# blahblahVCA_MB.net
KiCad netlist of a schematic drawn in EAGLE
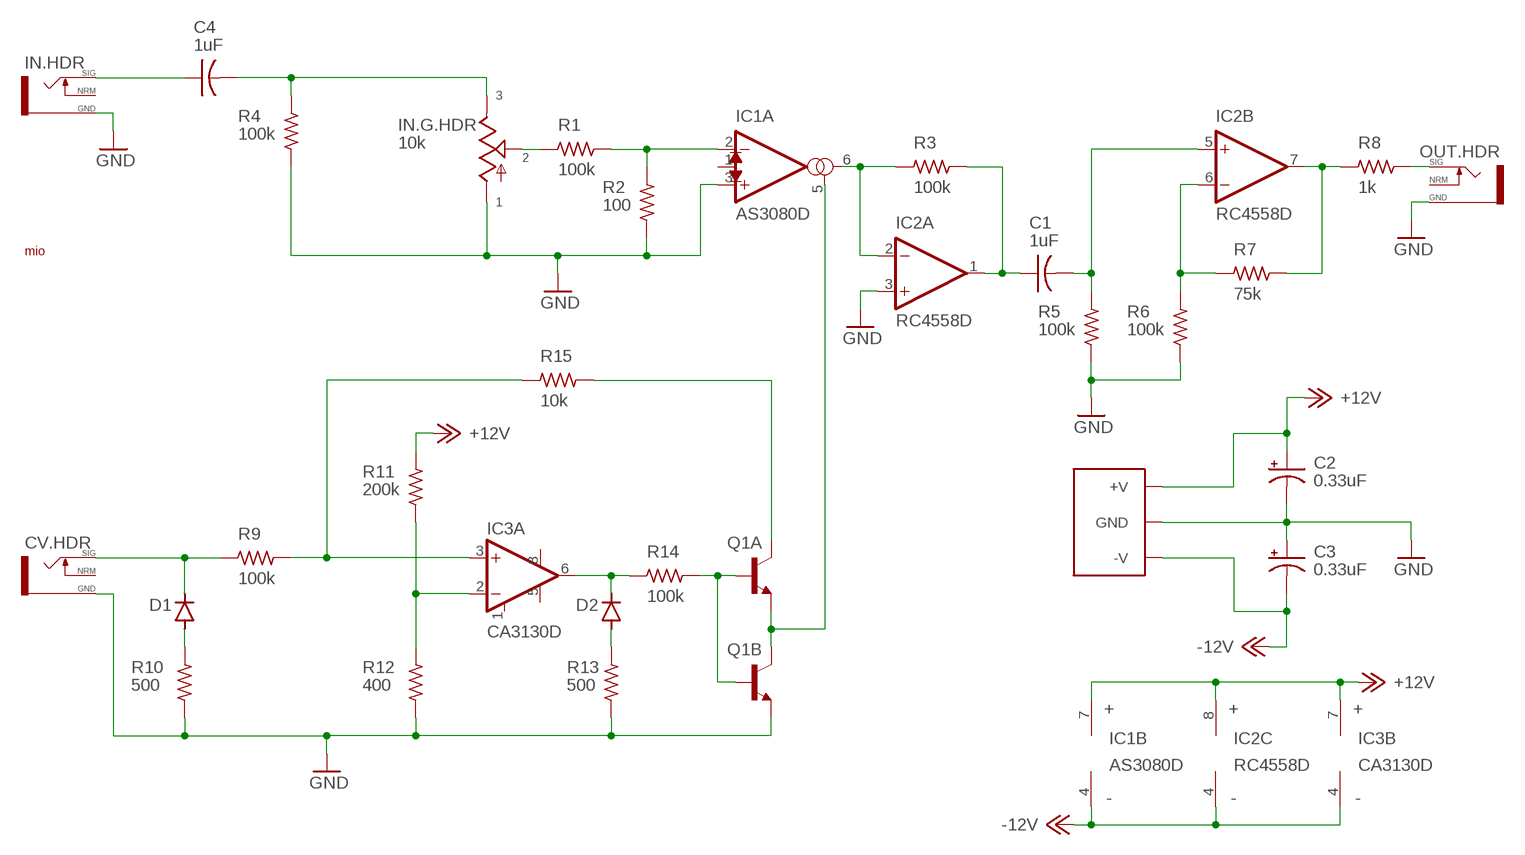
[diagram p0: schematic, sheet 1]

(export (version "E")
  (design (tool "Eeschema 10.0.6"))
  (components
    (comp (ref "C1")
      (value "1uF")
      (footprint "eagle-import:C05")
      (libsource (lib "eagle-import") (part "C-05"))
    )
    (comp (ref "C2")
      (value "0.33uF")
      (footprint "eagle-import:E025")
      (libsource (lib "eagle-import") (part "CPOL-E025"))
    )
    (comp (ref "C3")
      (value "0.33uF")
      (footprint "eagle-import:E025")
      (libsource (lib "eagle-import") (part "CPOL-E025"))
    )
    (comp (ref "C4")
      (value "1uF")
      (footprint "eagle-import:C05")
      (libsource (lib "eagle-import") (part "C-05"))
    )
    (comp (ref "CV.HDR")
      (value "MONOHDR")
      (footprint "eagle-import:HEADER")
      (libsource (lib "eagle-import") (part "MONOHDR"))
    )
    (comp (ref "D1")
      (value "D-123")
      (footprint "eagle-import:SOD-123")
      (libsource (lib "eagle-import") (part "D-123"))
    )
    (comp (ref "D2")
      (value "D-123")
      (footprint "eagle-import:SOD-123")
      (libsource (lib "eagle-import") (part "D-123"))
    )
    (comp (ref "IC1")
      (value "AS3080D")
      (footprint "eagle-import:DIL08")
      (libsource (lib "eagle-import") (part "AS3080D"))
    )
    (comp (ref "IC2")
      (value "RC4558D")
      (footprint "eagle-import:DIL08")
      (libsource (lib "eagle-import") (part "RC4558D"))
    )
    (comp (ref "IC3")
      (value "CA3130D")
      (footprint "eagle-import:DIL08")
      (libsource (lib "eagle-import") (part "CA3130D"))
    )
    (comp (ref "IN.G.HDR")
      (value "10k")
      (footprint "eagle-import:HEADER")
      (libsource (lib "eagle-import") (part "PHDR"))
    )
    (comp (ref "IN.HDR")
      (value "MONOHDR")
      (footprint "eagle-import:HEADER")
      (libsource (lib "eagle-import") (part "MONOHDR"))
    )
    (comp (ref "OUT.HDR")
      (value "MONOHDR")
      (footprint "eagle-import:HEADER")
      (libsource (lib "eagle-import") (part "MONOHDR"))
    )
    (comp (ref "Q1")
      (value "BCM847DS")
      (footprint "eagle-import:SOT-23-6")
      (libsource (lib "eagle-import") (part "BCM847DS"))
    )
    (comp (ref "R1")
      (value "100k")
      (footprint "eagle-import:R1206")
      (libsource (lib "eagle-import") (part "R-1206"))
    )
    (comp (ref "R2")
      (value "100")
      (footprint "eagle-import:R1206")
      (libsource (lib "eagle-import") (part "R-1206"))
    )
    (comp (ref "R3")
      (value "100k")
      (footprint "eagle-import:R1206")
      (libsource (lib "eagle-import") (part "R-1206"))
    )
    (comp (ref "R4")
      (value "100k")
      (footprint "eagle-import:R1206")
      (libsource (lib "eagle-import") (part "R-1206"))
    )
    (comp (ref "R5")
      (value "100k")
      (footprint "eagle-import:R1206")
      (libsource (lib "eagle-import") (part "R-1206"))
    )
    (comp (ref "R6")
      (value "100k")
      (footprint "eagle-import:R1206")
      (libsource (lib "eagle-import") (part "R-1206"))
    )
    (comp (ref "R7")
      (value "75k")
      (footprint "eagle-import:R1206")
      (libsource (lib "eagle-import") (part "R-1206"))
    )
    (comp (ref "R8")
      (value "1k")
      (footprint "eagle-import:R1206")
      (libsource (lib "eagle-import") (part "R-1206"))
    )
    (comp (ref "R9")
      (value "100k")
      (footprint "eagle-import:R1206")
      (libsource (lib "eagle-import") (part "R-1206"))
    )
    (comp (ref "R10")
      (value "500")
      (footprint "eagle-import:R1206")
      (libsource (lib "eagle-import") (part "R-1206"))
    )
    (comp (ref "R11")
      (value "200k")
      (footprint "eagle-import:R1206")
      (libsource (lib "eagle-import") (part "R-1206"))
    )
    (comp (ref "R12")
      (value "400")
      (footprint "eagle-import:R1206")
      (libsource (lib "eagle-import") (part "R-1206"))
    )
    (comp (ref "R13")
      (value "500")
      (footprint "eagle-import:R1206")
      (libsource (lib "eagle-import") (part "R-1206"))
    )
    (comp (ref "R14")
      (value "100k")
      (footprint "eagle-import:R1206")
      (libsource (lib "eagle-import") (part "R-1206"))
    )
    (comp (ref "R15")
      (value "10k")
      (footprint "eagle-import:R1206")
      (libsource (lib "eagle-import") (part "R-1206"))
    )
    (comp (ref "U$1")
      (value "10PIN-PWR")
      (footprint "eagle-import:10PIN-HEADER")
      (libsource (lib "eagle-import") (part "10PIN-PWR"))
    )
    (comp (ref "U$2")
      (value "MIO")
      (footprint "eagle-import:MIO")
      (libsource (lib "eagle-import") (part "MIO"))
    )
  )
  (nets
    (net (code "1") (name "+12V") (class "Default")
      (node (ref "C2") (pin "+") (pinfunction "+_+") (pintype "passive"))
      (node (ref "IC1") (pin "7") (pinfunction "V+_7") (pintype "power_in"))
      (node (ref "IC2") (pin "8") (pinfunction "V+_8") (pintype "power_in"))
      (node (ref "IC3") (pin "7") (pinfunction "V+_7") (pintype "power_in"))
      (node (ref "R11") (pin "2") (pinfunction "2_2") (pintype "passive"))
      (node (ref "U$1") (pin "10") (pinfunction "+V_10") (pintype "bidirectional"))
      (node (ref "U$1") (pin "9") (pinfunction "+V_9") (pintype "bidirectional"))
    )
    (net (code "2") (name "-12V") (class "Default")
      (node (ref "C3") (pin "-") (pinfunction "-_-") (pintype "passive"))
      (node (ref "IC1") (pin "4") (pinfunction "V-_4") (pintype "power_in"))
      (node (ref "IC2") (pin "4") (pinfunction "V-_4") (pintype "power_in"))
      (node (ref "IC3") (pin "4") (pinfunction "V-_4") (pintype "power_in"))
      (node (ref "U$1") (pin "1") (pinfunction "-V_1") (pintype "bidirectional"))
      (node (ref "U$1") (pin "2") (pinfunction "-V_2") (pintype "bidirectional"))
    )
    (net (code "3") (name "GND") (class "Default")
      (node (ref "C2") (pin "-") (pinfunction "-_-") (pintype "passive"))
      (node (ref "C3") (pin "+") (pinfunction "+_+") (pintype "passive"))
      (node (ref "CV.HDR") (pin "GND") (pinfunction "SLEEVE-GND_GND") (pintype "passive"))
      (node (ref "IC1") (pin "3") (pinfunction "NON-INVERTING(+)_3") (pintype "input"))
      (node (ref "IC2") (pin "3") (pinfunction "NON-INVERTING(+)_3") (pintype "input"))
      (node (ref "IN.G.HDR") (pin "1") (pinfunction "1_1") (pintype "passive"))
      (node (ref "IN.HDR") (pin "GND") (pinfunction "SLEEVE-GND_GND") (pintype "passive"))
      (node (ref "OUT.HDR") (pin "GND") (pinfunction "SLEEVE-GND_GND") (pintype "passive"))
      (node (ref "Q1") (pin "4") (pinfunction "E_4") (pintype "bidirectional"))
      (node (ref "R10") (pin "1") (pinfunction "1_1") (pintype "passive"))
      (node (ref "R12") (pin "1") (pinfunction "1_1") (pintype "passive"))
      (node (ref "R13") (pin "1") (pinfunction "1_1") (pintype "passive"))
      (node (ref "R2") (pin "1") (pinfunction "1_1") (pintype "passive"))
      (node (ref "R4") (pin "1") (pinfunction "1_1") (pintype "passive"))
      (node (ref "R5") (pin "1") (pinfunction "1_1") (pintype "passive"))
      (node (ref "R6") (pin "1") (pinfunction "1_1") (pintype "passive"))
      (node (ref "U$1") (pin "3") (pinfunction "GND_3") (pintype "bidirectional"))
      (node (ref "U$1") (pin "4") (pinfunction "GND_4") (pintype "bidirectional"))
      (node (ref "U$1") (pin "5") (pinfunction "GND_5") (pintype "bidirectional"))
      (node (ref "U$1") (pin "6") (pinfunction "GND_6") (pintype "bidirectional"))
      (node (ref "U$1") (pin "7") (pinfunction "GND_7") (pintype "bidirectional"))
      (node (ref "U$1") (pin "8") (pinfunction "GND_8") (pintype "bidirectional"))
    )
    (net (code "4") (name "Net-(C4-Pad1)") (class "Default")
      (node (ref "C4") (pin "1") (pinfunction "1_1") (pintype "passive"))
      (node (ref "IN.HDR") (pin "TIP-SIG") (pinfunction "TIP-SIG_TIP-SIG") (pintype "passive"))
    )
    (net (code "5") (name "Net-(C4-Pad2)") (class "Default")
      (node (ref "C4") (pin "2") (pinfunction "2_2") (pintype "passive"))
      (node (ref "IN.G.HDR") (pin "3") (pinfunction "3_3") (pintype "passive"))
      (node (ref "R4") (pin "2") (pinfunction "2_2") (pintype "passive"))
    )
    (net (code "6") (name "Net-(CV.HDR-PadTIP-SIG)") (class "Default")
      (node (ref "CV.HDR") (pin "TIP-SIG") (pinfunction "TIP-SIG_TIP-SIG") (pintype "passive"))
      (node (ref "D1") (pin "C") (pinfunction "C_C") (pintype "passive"))
      (node (ref "R9") (pin "1") (pinfunction "1_1") (pintype "passive"))
    )
    (net (code "7") (name "Net-(D1-PadA)") (class "Default")
      (node (ref "D1") (pin "A") (pinfunction "A_A") (pintype "passive"))
      (node (ref "R10") (pin "2") (pinfunction "2_2") (pintype "passive"))
    )
    (net (code "8") (name "Net-(D2-PadA)") (class "Default")
      (node (ref "D2") (pin "A") (pinfunction "A_A") (pintype "passive"))
      (node (ref "R13") (pin "2") (pinfunction "2_2") (pintype "passive"))
    )
    (net (code "9") (name "Net-(IC1A-I-BIAS)") (class "Default")
      (node (ref "IC1") (pin "5") (pinfunction "I-BIAS_5") (pintype "input"))
      (node (ref "Q1") (pin "1") (pinfunction "E_1") (pintype "bidirectional"))
      (node (ref "Q1") (pin "3") (pinfunction "C_3") (pintype "bidirectional"))
    )
    (net (code "10") (name "Net-(IC1A-INVERTING(-))") (class "Default")
      (node (ref "IC1") (pin "2") (pinfunction "INVERTING(-)_2") (pintype "input"))
      (node (ref "R1") (pin "2") (pinfunction "2_2") (pintype "passive"))
      (node (ref "R2") (pin "2") (pinfunction "2_2") (pintype "passive"))
    )
    (net (code "11") (name "Net-(IC1A-OUT)") (class "Default")
      (node (ref "IC1") (pin "6") (pinfunction "OUT_6") (pintype "output"))
      (node (ref "IC2") (pin "2") (pinfunction "INVERTING(-)_2") (pintype "input"))
      (node (ref "R3") (pin "1") (pinfunction "1_1") (pintype "passive"))
    )
    (net (code "12") (name "Net-(IC2A-OUT)") (class "Default")
      (node (ref "C1") (pin "1") (pinfunction "1_1") (pintype "passive"))
      (node (ref "IC2") (pin "1") (pinfunction "OUT_1") (pintype "output"))
      (node (ref "R3") (pin "2") (pinfunction "2_2") (pintype "passive"))
    )
    (net (code "13") (name "Net-(IC2B-INVERTING(-))") (class "Default")
      (node (ref "IC2") (pin "6") (pinfunction "INVERTING(-)_6") (pintype "input"))
      (node (ref "R6") (pin "2") (pinfunction "2_2") (pintype "passive"))
      (node (ref "R7") (pin "1") (pinfunction "1_1") (pintype "passive"))
    )
    (net (code "14") (name "Net-(IC2B-NON-INVERTING(+))") (class "Default")
      (node (ref "C1") (pin "2") (pinfunction "2_2") (pintype "passive"))
      (node (ref "IC2") (pin "5") (pinfunction "NON-INVERTING(+)_5") (pintype "input"))
      (node (ref "R5") (pin "2") (pinfunction "2_2") (pintype "passive"))
    )
    (net (code "15") (name "Net-(IC2B-OUT)") (class "Default")
      (node (ref "IC2") (pin "7") (pinfunction "OUT_7") (pintype "output"))
      (node (ref "R7") (pin "2") (pinfunction "2_2") (pintype "passive"))
      (node (ref "R8") (pin "1") (pinfunction "1_1") (pintype "passive"))
    )
    (net (code "16") (name "Net-(IC3A-INVERTINGA(-))") (class "Default")
      (node (ref "IC3") (pin "2") (pinfunction "INVERTINGA(-)_2") (pintype "input"))
      (node (ref "R11") (pin "1") (pinfunction "1_1") (pintype "passive"))
      (node (ref "R12") (pin "2") (pinfunction "2_2") (pintype "passive"))
    )
    (net (code "17") (name "Net-(IC3A-NON-INVERTING(+))") (class "Default")
      (node (ref "IC3") (pin "3") (pinfunction "NON-INVERTING(+)_3") (pintype "input"))
      (node (ref "R15") (pin "1") (pinfunction "1_1") (pintype "passive"))
      (node (ref "R9") (pin "2") (pinfunction "2_2") (pintype "passive"))
    )
    (net (code "18") (name "Net-(IC3A-OUT)") (class "Default")
      (node (ref "D2") (pin "C") (pinfunction "C_C") (pintype "passive"))
      (node (ref "IC3") (pin "6") (pinfunction "OUT_6") (pintype "output"))
      (node (ref "R14") (pin "1") (pinfunction "1_1") (pintype "passive"))
    )
    (net (code "19") (name "Net-(IN.G.HDR-Pad2)") (class "Default")
      (node (ref "IN.G.HDR") (pin "2") (pinfunction "2_2") (pintype "passive"))
      (node (ref "R1") (pin "1") (pinfunction "1_1") (pintype "passive"))
    )
    (net (code "20") (name "Net-(OUT.HDR-PadTIP-SIG)") (class "Default")
      (node (ref "OUT.HDR") (pin "TIP-SIG") (pinfunction "TIP-SIG_TIP-SIG") (pintype "passive"))
      (node (ref "R8") (pin "2") (pinfunction "2_2") (pintype "passive"))
    )
    (net (code "21") (name "Net-(Q1A-B)") (class "Default")
      (node (ref "Q1") (pin "2") (pinfunction "B_2") (pintype "bidirectional"))
      (node (ref "Q1") (pin "5") (pinfunction "B_5") (pintype "bidirectional"))
      (node (ref "R14") (pin "2") (pinfunction "2_2") (pintype "passive"))
    )
    (net (code "22") (name "Net-(Q1A-C)") (class "Default")
      (node (ref "Q1") (pin "6") (pinfunction "C_6") (pintype "bidirectional"))
      (node (ref "R15") (pin "2") (pinfunction "2_2") (pintype "passive"))
    )
    (net (code "23") (name "unconnected-(CV.HDR-SWITCH-NORM-PadNORM)") (class "Default")
      (node (ref "CV.HDR") (pin "NORM") (pinfunction "SWITCH-NORM_NORM") (pintype "passive"))
    )
    (net (code "24") (name "unconnected-(IC1A-D-BIAS-Pad1)") (class "Default")
      (node (ref "IC1") (pin "1") (pinfunction "D-BIAS_1") (pintype "input"))
    )
    (net (code "25") (name "unconnected-(IC3A-NULL(1)-Pad1)") (class "Default")
      (node (ref "IC3") (pin "1") (pinfunction "NULL(1)_1") (pintype "input"))
    )
    (net (code "26") (name "unconnected-(IC3A-NULL(5)-Pad5)") (class "Default")
      (node (ref "IC3") (pin "5") (pinfunction "NULL(5)_5") (pintype "input"))
    )
    (net (code "27") (name "unconnected-(IC3A-STRB-Pad8)") (class "Default")
      (node (ref "IC3") (pin "8") (pinfunction "STRB_8") (pintype "input"))
    )
    (net (code "28") (name "unconnected-(IN.HDR-SWITCH-NORM-PadNORM)") (class "Default")
      (node (ref "IN.HDR") (pin "NORM") (pinfunction "SWITCH-NORM_NORM") (pintype "passive"))
    )
    (net (code "29") (name "unconnected-(OUT.HDR-SWITCH-NORM-PadNORM)") (class "Default")
      (node (ref "OUT.HDR") (pin "NORM") (pinfunction "SWITCH-NORM_NORM") (pintype "passive"))
    )
  )
)
